# Leaf_Adapter.net
KiCad netlist of a schematic drawn in Altium Designer
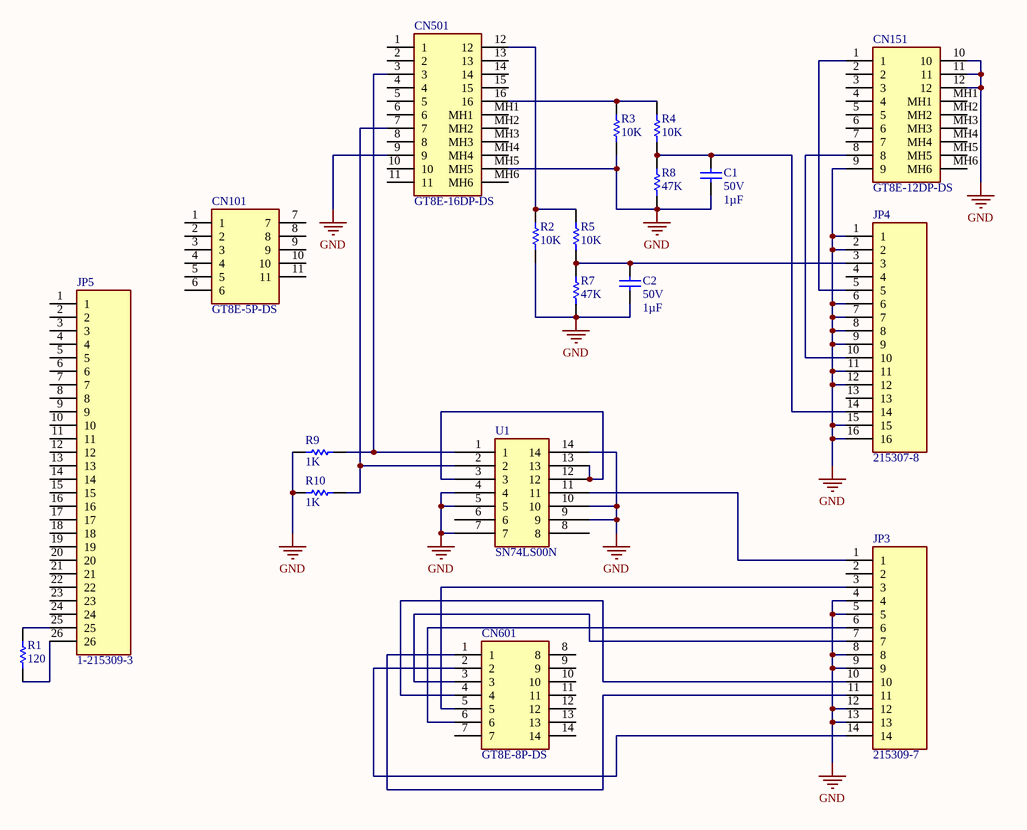
[diagram p0: Leaf_Adapter.SchDoc]

(export (version "E")
  (design (tool "Eeschema 10.0.6"))
  (components
    (comp (ref "C1")
      (value "C330C105M5U5TA")
      (footprint "KEMT-C330C105M5U5TA")
      (description "Ceramic Capacitor, 1 uF, +/- 20%, 50 V, -10 to 85 degC, 2-Pin THD, RoHS, Bulk")
      (fields
        (field (name "TOLERANCE") "±20%")
        (field (name "MANUFACTURER") "Kemet")
        (field (name "VOLTAGE - RATED") "50V")
        (field (name "CAPACITANCE") "1µF")
      )
      (libsource (lib "Leaf_Adapter") (part "CMP-2000-06056-1"))
    )
    (comp (ref "C2")
      (value "C330C105M5U5TA")
      (footprint "KEMT-C330C105M5U5TA")
      (description "Ceramic Capacitor, 1 uF, +/- 20%, 50 V, -10 to 85 degC, 2-Pin THD, RoHS, Bulk")
      (fields
        (field (name "TOLERANCE") "±20%")
        (field (name "MANUFACTURER") "Kemet")
        (field (name "VOLTAGE - RATED") "50V")
        (field (name "CAPACITANCE") "1µF")
      )
      (libsource (lib "Leaf_Adapter") (part "CMP-2000-06056-1"))
    )
    (comp (ref "CN101")
      (value "GT8E-5P-DS")
      (footprint "SamacSys:GT8E5PDS")
      (description "Connector")
      (libsource (lib "*") (part "GT8E-5P-DS"))
    )
    (comp (ref "CN151")
      (value "GT8E-12DP-DS")
      (footprint "SamacSys:GT8E12DPDS")
      (description "Connector")
      (libsource (lib "*") (part "GT8E-12DP-DS"))
    )
    (comp (ref "CN501")
      (value "GT8E-16DP-DS")
      (footprint "GT8E16DPDS")
      (description "Connector")
      (fields (field (name "MANUFACTURER_PART_NUMBER") "GT8E-12DP-DS"))
      (libsource (lib "Leaf_Adapter") (part "GT8E-16DP-DS"))
    )
    (comp (ref "CN601")
      (value "GT8E-8P-DS")
      (footprint "SamacSys:GT8E8PDS")
      (description "Connector")
      (libsource (lib "*") (part "GT8E-8P-DS"))
    )
    (comp (ref "JP3")
      (value "215309-7")
      (footprint "TE_215309-7")
      (description "2X7P HV100 REC CON. TE, 8.5MM")
      (fields (field (name "MF") "TE Connectivity"))
      (libsource (lib "Leaf_Adapter") (part "215309-7"))
    )
    (comp (ref "JP4")
      (value "215307-8")
      (footprint "TE_215307-8")
      (libsource (lib "Leaf_Adapter") (part "215307-8"))
    )
    (comp (ref "JP5")
      (value "1-215309-3")
      (footprint "TE_1-215309-3")
      (libsource (lib "Leaf_Adapter") (part "1-215309-3"))
    )
    (comp (ref "R1")
      (value "MRS25000C1200FC100")
      (footprint "RESA60-630X240")
      (description "RES 120 OHM 1% 0.6W AXIAL")
      (fields
        (field (name "TOLERANCE") "1%")
        (field (name "MANUFACTURER") "Vishay Beyschlag/Draloric/BC Components")
        (field (name "RESISTANCE") "120")
      )
      (libsource (lib "Leaf_Adapter") (part "MRS25000C1200FC100"))
    )
    (comp (ref "R2")
      (value "MFR-25FBF5210K")
      (footprint "RESA60-630X240")
      (description "Axial Resistor, 10 KOhm, +/- 1%, 0.25 W, -55 to 155 degC, 2-Pin THD, RoHS, Bulk")
      (fields
        (field (name "TOLERANCE") "1%")
        (field (name "MANUFACTURER") "Yageo")
        (field (name "RESISTANCE") "10K")
      )
      (libsource (lib "Leaf_Adapter") (part "CMP-1659-00074-2"))
    )
    (comp (ref "R3")
      (value "MFR-25FBF5210K")
      (footprint "RESA60-630X240")
      (description "Axial Resistor, 10 KOhm, +/- 1%, 0.25 W, -55 to 155 degC, 2-Pin THD, RoHS, Bulk")
      (fields
        (field (name "TOLERANCE") "1%")
        (field (name "MANUFACTURER") "Yageo")
        (field (name "RESISTANCE") "10K")
      )
      (libsource (lib "Leaf_Adapter") (part "CMP-1659-00074-2"))
    )
    (comp (ref "R4")
      (value "MFR-25FBF5210K")
      (footprint "RESA60-630X240")
      (description "Axial Resistor, 10 KOhm, +/- 1%, 0.25 W, -55 to 155 degC, 2-Pin THD, RoHS, Bulk")
      (fields
        (field (name "TOLERANCE") "1%")
        (field (name "MANUFACTURER") "Yageo")
        (field (name "RESISTANCE") "10K")
      )
      (libsource (lib "Leaf_Adapter") (part "CMP-1659-00074-2"))
    )
    (comp (ref "R5")
      (value "MFR-25FBF5210K")
      (footprint "RESA60-630X240")
      (description "Axial Resistor, 10 KOhm, +/- 1%, 0.25 W, -55 to 155 degC, 2-Pin THD, RoHS, Bulk")
      (fields
        (field (name "TOLERANCE") "1%")
        (field (name "MANUFACTURER") "Yageo")
        (field (name "RESISTANCE") "10K")
      )
      (libsource (lib "Leaf_Adapter") (part "CMP-1659-00074-2"))
    )
    (comp (ref "R7")
      (value "MRS25000C4702FC100")
      (footprint "RESA60-630X240")
      (description "RES 47K OHM 0.6W 1% AXIAL")
      (fields
        (field (name "TOLERANCE") "1%")
        (field (name "MANUFACTURER") "Vishay Beyschlag/Draloric/BC Components")
        (field (name "RESISTANCE") "47K")
      )
      (libsource (lib "Leaf_Adapter") (part "MRS25000C4702FC100"))
    )
    (comp (ref "R8")
      (value "MRS25000C4702FC100")
      (footprint "RESA60-630X240")
      (description "RES 47K OHM 0.6W 1% AXIAL")
      (fields
        (field (name "TOLERANCE") "1%")
        (field (name "MANUFACTURER") "Vishay Beyschlag/Draloric/BC Components")
        (field (name "RESISTANCE") "47K")
      )
      (libsource (lib "Leaf_Adapter") (part "MRS25000C4702FC100"))
    )
    (comp (ref "R9")
      (value "MFR-25FBF52-1K")
      (footprint "RESA60-630X240")
      (description "Axial Resistor, 1 KOhm, +/- 1%, 250 mW, -55 to 155 degC, 2-Pin THD, RoHS, Bulk")
      (fields (field (name "TOLERANCE") "1%") (field (name "RESISTANCE") "1K"))
      (libsource (lib "Leaf_Adapter") (part "CMP-1659-00075-1"))
    )
    (comp (ref "R10")
      (value "MFR-25FBF52-1K")
      (footprint "RESA60-630X240")
      (description "Axial Resistor, 1 KOhm, +/- 1%, 250 mW, -55 to 155 degC, 2-Pin THD, RoHS, Bulk")
      (fields (field (name "TOLERANCE") "1%") (field (name "RESISTANCE") "1K"))
      (libsource (lib "Leaf_Adapter") (part "CMP-1659-00075-1"))
    )
    (comp (ref "U1")
      (value "SN74LS00N")
      (footprint "N0014A")
      (description "IC GATE NAND 4CH 2-INP 14DIP")
      (fields (field (name "MANUFACTURER") "Texas Instruments"))
      (libsource (lib "Leaf_Adapter") (part "SN74LS00N"))
    )
  )
  (nets
    (net (code "1") (name "GND") (class "Default")
      (node (ref "C1") (pin "1") (pinfunction "1_1") (pintype "passive"))
      (node (ref "C2") (pin "1") (pinfunction "1_1") (pintype "passive"))
      (node (ref "CN151") (pin "10") (pinfunction "10_10") (pintype "passive"))
      (node (ref "CN151") (pin "11") (pinfunction "11_11") (pintype "passive"))
      (node (ref "CN151") (pin "12") (pinfunction "12_12") (pintype "passive"))
      (node (ref "CN151") (pin "9") (pinfunction "9_9") (pintype "passive"))
      (node (ref "CN501") (pin "9") (pinfunction "9_9") (pintype "passive"))
      (node (ref "CN501") (pin "MH5") (pinfunction "MH5_MH5") (pintype "passive"))
      (node (ref "JP3") (pin "12") (pinfunction "12_12") (pintype "passive"))
      (node (ref "JP3") (pin "13") (pinfunction "13_13") (pintype "passive"))
      (node (ref "JP3") (pin "4") (pinfunction "4_4") (pintype "passive"))
      (node (ref "JP3") (pin "5") (pinfunction "5_5") (pintype "passive"))
      (node (ref "JP3") (pin "8") (pinfunction "8_8") (pintype "passive"))
      (node (ref "JP3") (pin "9") (pinfunction "9_9") (pintype "passive"))
      (node (ref "JP4") (pin "1") (pinfunction "1_1") (pintype "passive"))
      (node (ref "JP4") (pin "11") (pinfunction "11_11") (pintype "passive"))
      (node (ref "JP4") (pin "12") (pinfunction "12_12") (pintype "passive"))
      (node (ref "JP4") (pin "15") (pinfunction "15_15") (pintype "passive"))
      (node (ref "JP4") (pin "16") (pinfunction "16_16") (pintype "passive"))
      (node (ref "JP4") (pin "2") (pinfunction "2_2") (pintype "passive"))
      (node (ref "JP4") (pin "6") (pinfunction "6_6") (pintype "passive"))
      (node (ref "JP4") (pin "7") (pinfunction "7_7") (pintype "passive"))
      (node (ref "JP4") (pin "8") (pinfunction "8_8") (pintype "passive"))
      (node (ref "JP4") (pin "9") (pinfunction "9_9") (pintype "passive"))
      (node (ref "R10") (pin "1") (pinfunction "1_1") (pintype "passive"))
      (node (ref "R2") (pin "1") (pinfunction "1_1") (pintype "passive"))
      (node (ref "R3") (pin "1") (pinfunction "1_1") (pintype "passive"))
      (node (ref "R7") (pin "1") (pinfunction "1_1") (pintype "passive"))
      (node (ref "R8") (pin "1") (pinfunction "1_1") (pintype "passive"))
      (node (ref "R9") (pin "1") (pinfunction "1_1") (pintype "passive"))
      (node (ref "U1") (pin "10") (pinfunction "10_10") (pintype "passive"))
      (node (ref "U1") (pin "14") (pinfunction "14_14") (pintype "passive"))
      (node (ref "U1") (pin "4") (pinfunction "4_4") (pintype "passive"))
      (node (ref "U1") (pin "5") (pinfunction "5_5") (pintype "passive"))
      (node (ref "U1") (pin "7") (pinfunction "7_7") (pintype "passive"))
      (node (ref "U1") (pin "9") (pinfunction "9_9") (pintype "passive"))
    )
    (net (code "2") (name "Net-(C1-Pad2)") (class "Default")
      (node (ref "C1") (pin "2") (pinfunction "2_2") (pintype "passive"))
      (node (ref "JP4") (pin "14") (pinfunction "14_14") (pintype "passive"))
      (node (ref "R4") (pin "1") (pinfunction "1_1") (pintype "passive"))
      (node (ref "R8") (pin "2") (pinfunction "2_2") (pintype "passive"))
    )
    (net (code "3") (name "Net-(C2-Pad2)") (class "Default")
      (node (ref "C2") (pin "2") (pinfunction "2_2") (pintype "passive"))
      (node (ref "JP4") (pin "3") (pinfunction "3_3") (pintype "passive"))
      (node (ref "R5") (pin "2") (pinfunction "2_2") (pintype "passive"))
      (node (ref "R7") (pin "2") (pinfunction "2_2") (pintype "passive"))
    )
    (net (code "4") (name "Net-(CN151-Pad1)") (class "Default")
      (node (ref "CN151") (pin "1") (pinfunction "1_1") (pintype "passive"))
      (node (ref "JP4") (pin "5") (pinfunction "5_5") (pintype "passive"))
    )
    (net (code "5") (name "Net-(CN151-Pad8)") (class "Default")
      (node (ref "CN151") (pin "8") (pinfunction "8_8") (pintype "passive"))
      (node (ref "JP4") (pin "10") (pinfunction "10_10") (pintype "passive"))
    )
    (net (code "6") (name "Net-(CN501-Pad3)") (class "Default")
      (node (ref "CN501") (pin "3") (pinfunction "3_3") (pintype "passive"))
      (node (ref "R9") (pin "2") (pinfunction "2_2") (pintype "passive"))
      (node (ref "U1") (pin "1") (pinfunction "1_1") (pintype "passive"))
    )
    (net (code "7") (name "Net-(CN501-Pad7)") (class "Default")
      (node (ref "CN501") (pin "7") (pinfunction "7_7") (pintype "passive"))
      (node (ref "R10") (pin "2") (pinfunction "2_2") (pintype "passive"))
      (node (ref "U1") (pin "2") (pinfunction "2_2") (pintype "passive"))
    )
    (net (code "8") (name "Net-(CN501-Pad12)") (class "Default")
      (node (ref "CN501") (pin "12") (pinfunction "12_12") (pintype "passive"))
      (node (ref "R2") (pin "2") (pinfunction "2_2") (pintype "passive"))
      (node (ref "R5") (pin "1") (pinfunction "1_1") (pintype "passive"))
    )
    (net (code "9") (name "Net-(CN501-Pad16)") (class "Default")
      (node (ref "CN501") (pin "16") (pinfunction "16_16") (pintype "passive"))
      (node (ref "R3") (pin "2") (pinfunction "2_2") (pintype "passive"))
      (node (ref "R4") (pin "2") (pinfunction "2_2") (pintype "passive"))
    )
    (net (code "10") (name "Net-(CN601-Pad1)") (class "Default")
      (node (ref "CN601") (pin "1") (pinfunction "1_1") (pintype "passive"))
      (node (ref "JP3") (pin "11") (pinfunction "11_11") (pintype "passive"))
    )
    (net (code "11") (name "Net-(CN601-Pad2)") (class "Default")
      (node (ref "CN601") (pin "2") (pinfunction "2_2") (pintype "passive"))
      (node (ref "JP3") (pin "14") (pinfunction "14_14") (pintype "passive"))
    )
    (net (code "12") (name "Net-(CN601-Pad3)") (class "Default")
      (node (ref "CN601") (pin "3") (pinfunction "3_3") (pintype "passive"))
      (node (ref "JP3") (pin "7") (pinfunction "7_7") (pintype "passive"))
    )
    (net (code "13") (name "Net-(CN601-Pad4)") (class "Default")
      (node (ref "CN601") (pin "4") (pinfunction "4_4") (pintype "passive"))
      (node (ref "JP3") (pin "10") (pinfunction "10_10") (pintype "passive"))
    )
    (net (code "14") (name "Net-(CN601-Pad5)") (class "Default")
      (node (ref "CN601") (pin "5") (pinfunction "5_5") (pintype "passive"))
      (node (ref "JP3") (pin "3") (pinfunction "3_3") (pintype "passive"))
    )
    (net (code "15") (name "Net-(CN601-Pad6)") (class "Default")
      (node (ref "CN601") (pin "6") (pinfunction "6_6") (pintype "passive"))
      (node (ref "JP3") (pin "6") (pinfunction "6_6") (pintype "passive"))
    )
    (net (code "16") (name "Net-(JP3-Pad1)") (class "Default")
      (node (ref "JP3") (pin "1") (pinfunction "1_1") (pintype "passive"))
      (node (ref "U1") (pin "11") (pinfunction "11_11") (pintype "passive"))
    )
    (net (code "17") (name "Net-(JP5-Pad25)") (class "Default")
      (node (ref "JP5") (pin "25") (pinfunction "25_25") (pintype "passive"))
      (node (ref "R1") (pin "2") (pinfunction "2_2") (pintype "passive"))
    )
    (net (code "18") (name "Net-(JP5-Pad26)") (class "Default")
      (node (ref "JP5") (pin "26") (pinfunction "26_26") (pintype "passive"))
      (node (ref "R1") (pin "1") (pinfunction "1_1") (pintype "passive"))
    )
    (net (code "19") (name "Net-(U1-Pad12)") (class "Default")
      (node (ref "U1") (pin "12") (pinfunction "12_12") (pintype "passive"))
      (node (ref "U1") (pin "13") (pinfunction "13_13") (pintype "passive"))
      (node (ref "U1") (pin "3") (pinfunction "3_3") (pintype "passive"))
    )
    (net (code "20") (name "unconnected-(CN101-Pad1)") (class "Default")
      (node (ref "CN101") (pin "1") (pinfunction "1_1") (pintype "passive"))
    )
    (net (code "21") (name "unconnected-(CN101-Pad2)") (class "Default")
      (node (ref "CN101") (pin "2") (pinfunction "2_2") (pintype "passive"))
    )
    (net (code "22") (name "unconnected-(CN101-Pad3)") (class "Default")
      (node (ref "CN101") (pin "3") (pinfunction "3_3") (pintype "passive"))
    )
    (net (code "23") (name "unconnected-(CN101-Pad4)") (class "Default")
      (node (ref "CN101") (pin "4") (pinfunction "4_4") (pintype "passive"))
    )
    (net (code "24") (name "unconnected-(CN101-Pad5)") (class "Default")
      (node (ref "CN101") (pin "5") (pinfunction "5_5") (pintype "passive"))
    )
    (net (code "25") (name "unconnected-(CN101-Pad6)") (class "Default")
      (node (ref "CN101") (pin "6") (pinfunction "6_6") (pintype "passive"))
    )
    (net (code "26") (name "unconnected-(CN101-Pad7)") (class "Default")
      (node (ref "CN101") (pin "7") (pinfunction "7_7") (pintype "passive"))
    )
    (net (code "27") (name "unconnected-(CN101-Pad8)") (class "Default")
      (node (ref "CN101") (pin "8") (pinfunction "8_8") (pintype "passive"))
    )
    (net (code "28") (name "unconnected-(CN101-Pad9)") (class "Default")
      (node (ref "CN101") (pin "9") (pinfunction "9_9") (pintype "passive"))
    )
    (net (code "29") (name "unconnected-(CN101-Pad10)") (class "Default")
      (node (ref "CN101") (pin "10") (pinfunction "10_10") (pintype "passive"))
    )
    (net (code "30") (name "unconnected-(CN101-Pad11)") (class "Default")
      (node (ref "CN101") (pin "11") (pinfunction "11_11") (pintype "passive"))
    )
    (net (code "31") (name "unconnected-(CN151-Pad2)") (class "Default")
      (node (ref "CN151") (pin "2") (pinfunction "2_2") (pintype "passive"))
    )
    (net (code "32") (name "unconnected-(CN151-Pad3)") (class "Default")
      (node (ref "CN151") (pin "3") (pinfunction "3_3") (pintype "passive"))
    )
    (net (code "33") (name "unconnected-(CN151-Pad4)") (class "Default")
      (node (ref "CN151") (pin "4") (pinfunction "4_4") (pintype "passive"))
    )
    (net (code "34") (name "unconnected-(CN151-Pad5)") (class "Default")
      (node (ref "CN151") (pin "5") (pinfunction "5_5") (pintype "passive"))
    )
    (net (code "35") (name "unconnected-(CN151-Pad6)") (class "Default")
      (node (ref "CN151") (pin "6") (pinfunction "6_6") (pintype "passive"))
    )
    (net (code "36") (name "unconnected-(CN151-Pad7)") (class "Default")
      (node (ref "CN151") (pin "7") (pinfunction "7_7") (pintype "passive"))
    )
    (net (code "37") (name "unconnected-(CN151-PadMH1)") (class "Default")
      (node (ref "CN151") (pin "MH1") (pinfunction "MH1_MH1") (pintype "passive"))
    )
    (net (code "38") (name "unconnected-(CN151-PadMH2)") (class "Default")
      (node (ref "CN151") (pin "MH2") (pinfunction "MH2_MH2") (pintype "passive"))
    )
    (net (code "39") (name "unconnected-(CN151-PadMH3)") (class "Default")
      (node (ref "CN151") (pin "MH3") (pinfunction "MH3_MH3") (pintype "passive"))
    )
    (net (code "40") (name "unconnected-(CN151-PadMH4)") (class "Default")
      (node (ref "CN151") (pin "MH4") (pinfunction "MH4_MH4") (pintype "passive"))
    )
    (net (code "41") (name "unconnected-(CN151-PadMH5)") (class "Default")
      (node (ref "CN151") (pin "MH5") (pinfunction "MH5_MH5") (pintype "passive"))
    )
    (net (code "42") (name "unconnected-(CN151-PadMH6)") (class "Default")
      (node (ref "CN151") (pin "MH6") (pinfunction "MH6_MH6") (pintype "passive"))
    )
    (net (code "43") (name "unconnected-(CN501-Pad1)") (class "Default")
      (node (ref "CN501") (pin "1") (pinfunction "1_1") (pintype "passive"))
    )
    (net (code "44") (name "unconnected-(CN501-Pad2)") (class "Default")
      (node (ref "CN501") (pin "2") (pinfunction "2_2") (pintype "passive"))
    )
    (net (code "45") (name "unconnected-(CN501-Pad4)") (class "Default")
      (node (ref "CN501") (pin "4") (pinfunction "4_4") (pintype "passive"))
    )
    (net (code "46") (name "unconnected-(CN501-Pad5)") (class "Default")
      (node (ref "CN501") (pin "5") (pinfunction "5_5") (pintype "passive"))
    )
    (net (code "47") (name "unconnected-(CN501-Pad6)") (class "Default")
      (node (ref "CN501") (pin "6") (pinfunction "6_6") (pintype "passive"))
    )
    (net (code "48") (name "unconnected-(CN501-Pad8)") (class "Default")
      (node (ref "CN501") (pin "8") (pinfunction "8_8") (pintype "passive"))
    )
    (net (code "49") (name "unconnected-(CN501-Pad10)") (class "Default")
      (node (ref "CN501") (pin "10") (pinfunction "10_10") (pintype "passive"))
    )
    (net (code "50") (name "unconnected-(CN501-Pad11)") (class "Default")
      (node (ref "CN501") (pin "11") (pinfunction "11_11") (pintype "passive"))
    )
    (net (code "51") (name "unconnected-(CN501-Pad13)") (class "Default")
      (node (ref "CN501") (pin "13") (pinfunction "13_13") (pintype "passive"))
    )
    (net (code "52") (name "unconnected-(CN501-Pad14)") (class "Default")
      (node (ref "CN501") (pin "14") (pinfunction "14_14") (pintype "passive"))
    )
    (net (code "53") (name "unconnected-(CN501-Pad15)") (class "Default")
      (node (ref "CN501") (pin "15") (pinfunction "15_15") (pintype "passive"))
    )
    (net (code "54") (name "unconnected-(CN501-PadMH1)") (class "Default")
      (node (ref "CN501") (pin "MH1") (pinfunction "MH1_MH1") (pintype "passive"))
    )
    (net (code "55") (name "unconnected-(CN501-PadMH2)") (class "Default")
      (node (ref "CN501") (pin "MH2") (pinfunction "MH2_MH2") (pintype "passive"))
    )
    (net (code "56") (name "unconnected-(CN501-PadMH3)") (class "Default")
      (node (ref "CN501") (pin "MH3") (pinfunction "MH3_MH3") (pintype "passive"))
    )
    (net (code "57") (name "unconnected-(CN501-PadMH4)") (class "Default")
      (node (ref "CN501") (pin "MH4") (pinfunction "MH4_MH4") (pintype "passive"))
    )
    (net (code "58") (name "unconnected-(CN501-PadMH6)") (class "Default")
      (node (ref "CN501") (pin "MH6") (pinfunction "MH6_MH6") (pintype "passive"))
    )
    (net (code "59") (name "unconnected-(CN601-Pad7)") (class "Default")
      (node (ref "CN601") (pin "7") (pinfunction "7_7") (pintype "passive"))
    )
    (net (code "60") (name "unconnected-(CN601-Pad8)") (class "Default")
      (node (ref "CN601") (pin "8") (pinfunction "8_8") (pintype "passive"))
    )
    (net (code "61") (name "unconnected-(CN601-Pad9)") (class "Default")
      (node (ref "CN601") (pin "9") (pinfunction "9_9") (pintype "passive"))
    )
    (net (code "62") (name "unconnected-(CN601-Pad10)") (class "Default")
      (node (ref "CN601") (pin "10") (pinfunction "10_10") (pintype "passive"))
    )
    (net (code "63") (name "unconnected-(CN601-Pad11)") (class "Default")
      (node (ref "CN601") (pin "11") (pinfunction "11_11") (pintype "passive"))
    )
    (net (code "64") (name "unconnected-(CN601-Pad12)") (class "Default")
      (node (ref "CN601") (pin "12") (pinfunction "12_12") (pintype "passive"))
    )
    (net (code "65") (name "unconnected-(CN601-Pad13)") (class "Default")
      (node (ref "CN601") (pin "13") (pinfunction "13_13") (pintype "passive"))
    )
    (net (code "66") (name "unconnected-(CN601-Pad14)") (class "Default")
      (node (ref "CN601") (pin "14") (pinfunction "14_14") (pintype "passive"))
    )
    (net (code "67") (name "unconnected-(JP3-Pad2)") (class "Default")
      (node (ref "JP3") (pin "2") (pinfunction "2_2") (pintype "passive"))
    )
    (net (code "68") (name "unconnected-(JP4-Pad4)") (class "Default")
      (node (ref "JP4") (pin "4") (pinfunction "4_4") (pintype "passive"))
    )
    (net (code "69") (name "unconnected-(JP4-Pad13)") (class "Default")
      (node (ref "JP4") (pin "13") (pinfunction "13_13") (pintype "passive"))
    )
    (net (code "70") (name "unconnected-(JP5-Pad1)") (class "Default")
      (node (ref "JP5") (pin "1") (pinfunction "1_1") (pintype "passive"))
    )
    (net (code "71") (name "unconnected-(JP5-Pad2)") (class "Default")
      (node (ref "JP5") (pin "2") (pinfunction "2_2") (pintype "passive"))
    )
    (net (code "72") (name "unconnected-(JP5-Pad3)") (class "Default")
      (node (ref "JP5") (pin "3") (pinfunction "3_3") (pintype "passive"))
    )
    (net (code "73") (name "unconnected-(JP5-Pad4)") (class "Default")
      (node (ref "JP5") (pin "4") (pinfunction "4_4") (pintype "passive"))
    )
    (net (code "74") (name "unconnected-(JP5-Pad5)") (class "Default")
      (node (ref "JP5") (pin "5") (pinfunction "5_5") (pintype "passive"))
    )
    (net (code "75") (name "unconnected-(JP5-Pad6)") (class "Default")
      (node (ref "JP5") (pin "6") (pinfunction "6_6") (pintype "passive"))
    )
    (net (code "76") (name "unconnected-(JP5-Pad7)") (class "Default")
      (node (ref "JP5") (pin "7") (pinfunction "7_7") (pintype "passive"))
    )
    (net (code "77") (name "unconnected-(JP5-Pad8)") (class "Default")
      (node (ref "JP5") (pin "8") (pinfunction "8_8") (pintype "passive"))
    )
    (net (code "78") (name "unconnected-(JP5-Pad9)") (class "Default")
      (node (ref "JP5") (pin "9") (pinfunction "9_9") (pintype "passive"))
    )
    (net (code "79") (name "unconnected-(JP5-Pad10)") (class "Default")
      (node (ref "JP5") (pin "10") (pinfunction "10_10") (pintype "passive"))
    )
    (net (code "80") (name "unconnected-(JP5-Pad11)") (class "Default")
      (node (ref "JP5") (pin "11") (pinfunction "11_11") (pintype "passive"))
    )
    (net (code "81") (name "unconnected-(JP5-Pad12)") (class "Default")
      (node (ref "JP5") (pin "12") (pinfunction "12_12") (pintype "passive"))
    )
    (net (code "82") (name "unconnected-(JP5-Pad13)") (class "Default")
      (node (ref "JP5") (pin "13") (pinfunction "13_13") (pintype "passive"))
    )
    (net (code "83") (name "unconnected-(JP5-Pad14)") (class "Default")
      (node (ref "JP5") (pin "14") (pinfunction "14_14") (pintype "passive"))
    )
    (net (code "84") (name "unconnected-(JP5-Pad15)") (class "Default")
      (node (ref "JP5") (pin "15") (pinfunction "15_15") (pintype "passive"))
    )
    (net (code "85") (name "unconnected-(JP5-Pad16)") (class "Default")
      (node (ref "JP5") (pin "16") (pinfunction "16_16") (pintype "passive"))
    )
    (net (code "86") (name "unconnected-(JP5-Pad17)") (class "Default")
      (node (ref "JP5") (pin "17") (pinfunction "17_17") (pintype "passive"))
    )
    (net (code "87") (name "unconnected-(JP5-Pad18)") (class "Default")
      (node (ref "JP5") (pin "18") (pinfunction "18_18") (pintype "passive"))
    )
    (net (code "88") (name "unconnected-(JP5-Pad19)") (class "Default")
      (node (ref "JP5") (pin "19") (pinfunction "19_19") (pintype "passive"))
    )
    (net (code "89") (name "unconnected-(JP5-Pad20)") (class "Default")
      (node (ref "JP5") (pin "20") (pinfunction "20_20") (pintype "passive"))
    )
    (net (code "90") (name "unconnected-(JP5-Pad21)") (class "Default")
      (node (ref "JP5") (pin "21") (pinfunction "21_21") (pintype "passive"))
    )
    (net (code "91") (name "unconnected-(JP5-Pad22)") (class "Default")
      (node (ref "JP5") (pin "22") (pinfunction "22_22") (pintype "passive"))
    )
    (net (code "92") (name "unconnected-(JP5-Pad23)") (class "Default")
      (node (ref "JP5") (pin "23") (pinfunction "23_23") (pintype "passive"))
    )
    (net (code "93") (name "unconnected-(JP5-Pad24)") (class "Default")
      (node (ref "JP5") (pin "24") (pinfunction "24_24") (pintype "passive"))
    )
    (net (code "94") (name "unconnected-(U1-Pad6)") (class "Default")
      (node (ref "U1") (pin "6") (pinfunction "6_6") (pintype "passive"))
    )
    (net (code "95") (name "unconnected-(U1-Pad8)") (class "Default")
      (node (ref "U1") (pin "8") (pinfunction "8_8") (pintype "passive"))
    )
  )
)
